# w13.net
KiCad netlist of a schematic drawn in EAGLE
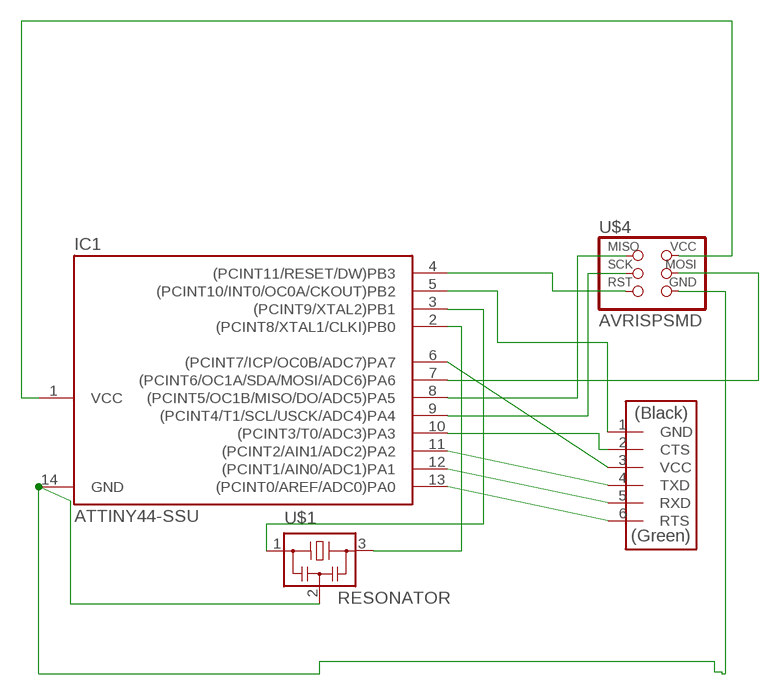
[diagram p0: schematic, sheet 1]

(export (version "E")
  (design (tool "Eeschema 10.0.6"))
  (components
    (comp (ref "IC1")
      (value "ATTINY44-SSU")
      (footprint "eagle-import:SOIC14")
      (libsource (lib "eagle-import") (part "ATTINY44-SSU"))
    )
    (comp (ref "U$1")
      (value "RESONATOR")
      (footprint "eagle-import:EFOBM")
      (libsource (lib "eagle-import") (part "RESONATOR"))
    )
    (comp (ref "U$3")
      (value "FTDI-SMD-HEADER")
      (footprint "eagle-import:1X06SMD")
      (libsource (lib "eagle-import") (part "FTDI-SMD-HEADER"))
    )
    (comp (ref "U$4")
      (value "AVRISPSMD")
      (footprint "eagle-import:2X03SMD")
      (libsource (lib "eagle-import") (part "AVRISPSMD"))
    )
  )
  (nets
    (net (code "1") (name "Net-(IC1-(PCINT0{slash}AREF{slash}ADC0)PA0)") (class "Default")
      (node (ref "IC1") (pin "13") (pinfunction "(PCINT0/AREF/ADC0)PA0_13") (pintype "bidirectional"))
      (node (ref "U$3") (pin "6") (pinfunction "RTS_6") (pintype "bidirectional"))
    )
    (net (code "2") (name "Net-(IC1-(PCINT1{slash}AIN0{slash}ADC1)PA1)") (class "Default")
      (node (ref "IC1") (pin "12") (pinfunction "(PCINT1/AIN0/ADC1)PA1_12") (pintype "bidirectional"))
      (node (ref "U$3") (pin "5") (pinfunction "RXD_5") (pintype "bidirectional"))
    )
    (net (code "3") (name "Net-(IC1-(PCINT2{slash}AIN1{slash}ADC2)PA2)") (class "Default")
      (node (ref "IC1") (pin "11") (pinfunction "(PCINT2/AIN1/ADC2)PA2_11") (pintype "bidirectional"))
      (node (ref "U$3") (pin "4") (pinfunction "TXD_4") (pintype "bidirectional"))
    )
    (net (code "4") (name "Net-(IC1-(PCINT3{slash}T0{slash}ADC3)PA3)") (class "Default")
      (node (ref "IC1") (pin "10") (pinfunction "(PCINT3/T0/ADC3)PA3_10") (pintype "bidirectional"))
      (node (ref "U$3") (pin "2") (pinfunction "CTS_2") (pintype "bidirectional"))
    )
    (net (code "5") (name "Net-(IC1-(PCINT4{slash}T1{slash}SCL{slash}USCK{slash}ADC4)PA4)") (class "Default")
      (node (ref "IC1") (pin "9") (pinfunction "(PCINT4/T1/SCL/USCK/ADC4)PA4_9") (pintype "bidirectional"))
      (node (ref "U$4") (pin "3") (pinfunction "SCK_3") (pintype "passive"))
    )
    (net (code "6") (name "Net-(IC1-(PCINT5{slash}OC1B{slash}MISO{slash}DO{slash}ADC5)PA5)") (class "Default")
      (node (ref "IC1") (pin "8") (pinfunction "(PCINT5/OC1B/MISO/DO/ADC5)PA5_8") (pintype "bidirectional"))
      (node (ref "U$4") (pin "1") (pinfunction "MISO_1") (pintype "passive"))
    )
    (net (code "7") (name "Net-(IC1-(PCINT6{slash}OC1A{slash}SDA{slash}MOSI{slash}ADC6)PA6)") (class "Default")
      (node (ref "IC1") (pin "7") (pinfunction "(PCINT6/OC1A/SDA/MOSI/ADC6)PA6_7") (pintype "bidirectional"))
      (node (ref "U$4") (pin "4") (pinfunction "MOSI_4") (pintype "passive"))
    )
    (net (code "8") (name "Net-(IC1-(PCINT7{slash}ICP{slash}OC0B{slash}ADC7)PA7)") (class "Default")
      (node (ref "IC1") (pin "6") (pinfunction "(PCINT7/ICP/OC0B/ADC7)PA7_6") (pintype "bidirectional"))
      (node (ref "U$3") (pin "3") (pinfunction "VCC_3") (pintype "bidirectional"))
    )
    (net (code "9") (name "Net-(IC1-(PCINT8{slash}XTAL1{slash}CLKI)PB0)") (class "Default")
      (node (ref "IC1") (pin "2") (pinfunction "(PCINT8/XTAL1/CLKI)PB0_2") (pintype "bidirectional"))
      (node (ref "U$1") (pin "3") (pinfunction "3_3") (pintype "passive"))
    )
    (net (code "10") (name "Net-(IC1-(PCINT9{slash}XTAL2)PB1)") (class "Default")
      (node (ref "IC1") (pin "3") (pinfunction "(PCINT9/XTAL2)PB1_3") (pintype "bidirectional"))
      (node (ref "U$1") (pin "1") (pinfunction "1_1") (pintype "passive"))
    )
    (net (code "11") (name "Net-(IC1-(PCINT10{slash}INT0{slash}OC0A{slash}CKOUT)PB2)") (class "Default")
      (node (ref "IC1") (pin "5") (pinfunction "(PCINT10/INT0/OC0A/CKOUT)PB2_5") (pintype "bidirectional"))
      (node (ref "U$3") (pin "1") (pinfunction "GND_1") (pintype "bidirectional"))
    )
    (net (code "12") (name "Net-(IC1-(PCINT11{slash}RESET{slash}DW)PB3)") (class "Default")
      (node (ref "IC1") (pin "4") (pinfunction "(PCINT11/RESET/DW)PB3_4") (pintype "bidirectional"))
      (node (ref "U$4") (pin "5") (pinfunction "RST_5") (pintype "passive"))
    )
    (net (code "13") (name "Net-(IC1-GND)") (class "Default")
      (node (ref "IC1") (pin "14") (pinfunction "GND_14") (pintype "power_in"))
      (node (ref "U$1") (pin "2") (pinfunction "2_2") (pintype "passive"))
      (node (ref "U$4") (pin "6") (pinfunction "GND_6") (pintype "passive"))
    )
    (net (code "14") (name "Net-(IC1-VCC)") (class "Default")
      (node (ref "IC1") (pin "1") (pinfunction "VCC_1") (pintype "power_in"))
      (node (ref "U$4") (pin "2") (pinfunction "VCC_2") (pintype "passive"))
    )
  )
)
